# Power.net
KiCad netlist of a schematic drawn in Altium Designer
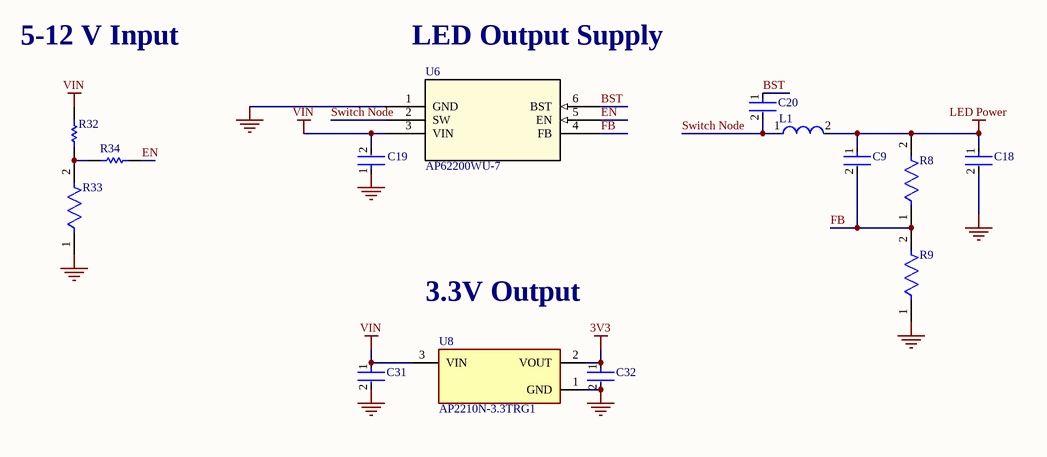
[diagram p0: Power.SchDoc]

(export (version "E")
  (design (tool "Eeschema 10.0.6"))
  (components
    (comp (ref "C9")
      (value "UMK105CG330JVHF")
      (footprint "FP-0402-L_1_0_0_05-W_0_5-MFG")
      (description "None")
      (fields (field (name "TOLERANCE") "5%"))
      (libsource (lib "Altium Content Vault") (part "b4654b650e69147ec39a6b967a45e02"))
    )
    (comp (ref "C18")
      (value "EMK316BB7226ML-T")
      (footprint "FP-1206-L_3_2_0_3-W_1_6_0-IPC_A")
      (description "None")
      (fields (field (name "TOLERANCE") "20%"))
      (libsource (lib "Altium Content Vault") (part "11868f565c42a9108669ba33697ecf6"))
    )
    (comp (ref "C19")
      (value "GRM188R6YA475KE15D")
      (footprint "FP-GRM188-0_2-IPC_C")
      (description "Chip Multilayer Ceramic Capacitors for General Purpose, 0603, 4.7uF, X5R, 15%, 10%, 35V")
      (fields (field (name "VOLTAGE") "35V") (field (name "TOLERANCE") "10%"))
      (libsource (lib "Altium Content Vault") (part "11868f565c42a9108669ba33697ecf6"))
    )
    (comp (ref "C20")
      (value "GRM155R71C224KA12D")
      (footprint "FP-GRM155-0_05-IPC_C")
      (description "Chip Multilayer Ceramic Capacitors for General Purpose, 0402, 0.22uF, X7R, 15%, 10%, 16V")
      (fields (field (name "VOLTAGE") "16V") (field (name "TOLERANCE") "10%"))
      (libsource (lib "Altium Content Vault") (part "02cd4be3c70576c341d710602a673aa"))
    )
    (comp (ref "C31")
      (value "GCM21BR71H105MA03L")
      (footprint "FP-GCM21B-0_15-MFG")
      (description "Ceramic Capacitor for Automotive 1uF ±20% 50VDC X7R 0805 Embossed T/R")
      (libsource (lib "Altium Content Vault") (part "02cd4be3c70576c341d710602a673aa"))
    )
    (comp (ref "C32")
      (value "GCJ21BR71E225KA01L")
      (footprint "FP-GCJ21B-0_3-MFG")
      (description "Multilayer Ceramic Capacitors MLCC - SMD/SMT 0805 2.2uF 10%, 25VDC,  X7R 15%")
      (libsource (lib "Altium Content Vault") (part "02cd4be3c70576c341d710602a673aa"))
    )
    (comp (ref "L1")
      (value "LQM21PN1R0NGRD")
      (footprint "FP-LQM21PH_G0-IPC_C")
      (description "Multilayer Type Inductor for Power Lines, 0805 (2012), 1μH, 30%, 0.0825Ω, 1.3A")
      (fields (field (name "TOLERANCE") "30%"))
      (libsource (lib "Altium Content Vault") (part "725321dda6339637d4d059423bc1c3c"))
    )
    (comp (ref "R8")
      (value "AC0402JR-07200KL")
      (footprint "FP-AC0402-IPC_B")
      (description "RES 200kΩ ±5% 0.063W 0402")
      (fields (field (name "TOLERANCE") "5%"))
      (libsource (lib "Altium Content Vault") (part "1029c3af85768c4190bb7ad29bc67b5"))
    )
    (comp (ref "R9")
      (value "RK73H1ERTTP4422F")
      (footprint "FP-RK73H1E-IPC_C")
      (description "44.2kΩ ±1% 0.1W Chip Resistor 0402 Flat Chip (Anti-Sulfuration) AEC-Q200 Qualified")
      (fields (field (name "TOLERANCE") "1%"))
      (libsource (lib "Altium Content Vault") (part "1029c3af85768c4190bb7ad29bc67b5"))
    )
    (comp (ref "R32")
      (value "ERJ-2GEJ204X")
      (footprint "RESC1005X40X25NL05T05")
      (fields (field (name "MANUFACTURER") "Panasonic"))
      (libsource (lib "Altium Content Vault") (part "RES"))
    )
    (comp (ref "R33")
      (value "CRCW040250K0FKED")
      (footprint "FP-CRCW0402-e3-IPC_A")
      (description "RES Thick Film, 50kΩ, 1%, 0.063W, 100ppm/°C, 0402")
      (fields (field (name "TOLERANCE") "1%"))
      (libsource (lib "Altium Content Vault") (part "1029c3af85768c4190bb7ad29bc67b5"))
    )
    (comp (ref "R34")
      (value "RC0402JR-100RL")
      (footprint "RESC1005X40X25NL05T10")
      (fields (field (name "MANUFACTURER") "Yageo"))
      (libsource (lib "Altium Content Vault") (part "RES"))
    )
    (comp (ref "U6")
      (value "AP62200WU-7")
      (footprint "TSOT26-WU_DIO")
      (description "No Description Available")
      (fields (field (name "COPYRIGHT") "Copyright (C) 2026 Ultra Librarian. All rights reserved."))
      (libsource (lib "AP62200WU-7") (part "AP62200WU-7"))
    )
    (comp (ref "U8")
      (value "AP2210N-3.3TRG1")
      (footprint "FP-SOT23-IPC_C")
      (description "IC REG LINEAR 3.3V 300MA SOT23-3")
      (libsource (lib "Altium Content Vault") (part "bd94623faa3c699494368a50adf163b"))
    )
  )
  (nets
    (net (code "1") (name "/BST") (class "Default")
      (node (ref "C20") (pin "1") (pinfunction "1_1") (pintype "passive"))
      (node (ref "U6") (pin "6") (pinfunction "BST_6") (pintype "input"))
    )
    (net (code "2") (name "/EN") (class "Default")
      (node (ref "R34") (pin "2") (pinfunction "2_2") (pintype "passive"))
      (node (ref "U6") (pin "5") (pinfunction "EN_5") (pintype "input"))
    )
    (net (code "3") (name "/FB") (class "Default")
      (node (ref "C9") (pin "2") (pinfunction "2_2") (pintype "passive"))
      (node (ref "R8") (pin "1") (pinfunction "1_1") (pintype "passive"))
      (node (ref "R9") (pin "2") (pinfunction "2_2") (pintype "passive"))
      (node (ref "U6") (pin "4") (pinfunction "FB_4") (pintype "passive"))
    )
    (net (code "4") (name "/Switch Node") (class "Default")
      (node (ref "C20") (pin "2") (pinfunction "2_2") (pintype "passive"))
      (node (ref "L1") (pin "1") (pinfunction "1_1") (pintype "passive"))
      (node (ref "U6") (pin "2") (pinfunction "SW_2") (pintype "passive"))
    )
    (net (code "5") (name "3V3") (class "Default")
      (node (ref "C32") (pin "1") (pinfunction "1_1") (pintype "passive"))
      (node (ref "U8") (pin "2") (pinfunction "VOUT_2") (pintype "power_in"))
    )
    (net (code "6") (name "GND") (class "Default")
      (node (ref "C18") (pin "2") (pinfunction "2_2") (pintype "passive"))
      (node (ref "C19") (pin "1") (pinfunction "1_1") (pintype "passive"))
      (node (ref "C31") (pin "2") (pinfunction "2_2") (pintype "passive"))
      (node (ref "C32") (pin "2") (pinfunction "2_2") (pintype "passive"))
      (node (ref "R33") (pin "1") (pinfunction "1_1") (pintype "passive"))
      (node (ref "R9") (pin "1") (pinfunction "1_1") (pintype "passive"))
      (node (ref "U6") (pin "1") (pinfunction "GND_1") (pintype "power_in"))
      (node (ref "U8") (pin "1") (pinfunction "GND_1") (pintype "power_in"))
    )
    (net (code "7") (name "LED Power") (class "Default")
      (node (ref "C18") (pin "1") (pinfunction "1_1") (pintype "passive"))
      (node (ref "C9") (pin "1") (pinfunction "1_1") (pintype "passive"))
      (node (ref "L1") (pin "2") (pinfunction "2_2") (pintype "passive"))
      (node (ref "R8") (pin "2") (pinfunction "2_2") (pintype "passive"))
    )
    (net (code "8") (name "Net-(R32-Pad1)") (class "Default")
      (node (ref "R32") (pin "1") (pinfunction "1_1") (pintype "passive"))
      (node (ref "R33") (pin "2") (pinfunction "2_2") (pintype "passive"))
      (node (ref "R34") (pin "1") (pinfunction "1_1") (pintype "passive"))
    )
    (net (code "9") (name "VIN") (class "Default")
      (node (ref "C19") (pin "2") (pinfunction "2_2") (pintype "passive"))
      (node (ref "C31") (pin "1") (pinfunction "1_1") (pintype "passive"))
      (node (ref "R32") (pin "2") (pinfunction "2_2") (pintype "passive"))
      (node (ref "U6") (pin "3") (pinfunction "VIN_3") (pintype "power_in"))
      (node (ref "U8") (pin "3") (pinfunction "VIN_3") (pintype "power_in"))
    )
  )
)
